# PIR_AM612.net
KiCad netlist of a schematic drawn in EAGLE
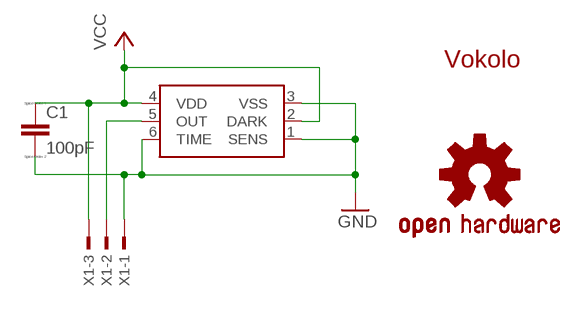
[diagram p0: schematic, sheet 1]

(export (version "E")
  (design (tool "Eeschema 10.0.6"))
  (components
    (comp (ref "C1")
      (value "100pF")
      (footprint "eagle-import:C0603")
      (libsource (lib "eagle-import") (part "CC0603"))
    )
    (comp (ref "LOGO1")
      (value "OSHW-LOGOS")
      (footprint "eagle-import:OSHW-LOGO-S")
      (libsource (lib "eagle-import") (part "OSHW-LOGOS"))
    )
    (comp (ref "U$2")
      (value "AM612")
      (footprint "eagle-import:TO5")
      (libsource (lib "eagle-import") (part "AM612"))
    )
    (comp (ref "U$3")
      (value "LOGO_VOKOLO9,7MM")
      (footprint "eagle-import:LOGO_VOKOLO_8MM")
      (libsource (lib "eagle-import") (part "LOGO_VOKOLO9,7MM"))
    )
    (comp (ref "X1")
      (value "TSW-103-07-G-S")
      (footprint "eagle-import:TSW-103-XX-G-S")
      (fields (field (name "MF") "Samtec Inc."))
      (libsource (lib "eagle-import") (part "TSW-103--G-S07"))
    )
  )
  (nets
    (net (code "1") (name "GND") (class "Default")
      (node (ref "C1") (pin "2") (pinfunction "2_2") (pintype "passive"))
      (node (ref "U$2") (pin "1") (pinfunction "SENS_1") (pintype "bidirectional"))
      (node (ref "U$2") (pin "3") (pinfunction "VSS_3") (pintype "bidirectional"))
      (node (ref "U$2") (pin "6") (pinfunction "TIME_6") (pintype "bidirectional"))
      (node (ref "X1") (pin "1") (pinfunction "1_1") (pintype "passive"))
    )
    (net (code "2") (name "Net-(U$2-OUT)") (class "Default")
      (node (ref "U$2") (pin "5") (pinfunction "OUT_5") (pintype "bidirectional"))
      (node (ref "X1") (pin "2") (pinfunction "1_2") (pintype "passive"))
    )
    (net (code "3") (name "VCC") (class "Default")
      (node (ref "C1") (pin "1") (pinfunction "1_1") (pintype "passive"))
      (node (ref "U$2") (pin "2") (pinfunction "DARK_2") (pintype "bidirectional"))
      (node (ref "U$2") (pin "4") (pinfunction "VDD_4") (pintype "bidirectional"))
      (node (ref "X1") (pin "3") (pinfunction "1_3") (pintype "passive"))
    )
  )
)
